# Non_Inverting_0603.net
KiCad netlist of a schematic drawn in EAGLE
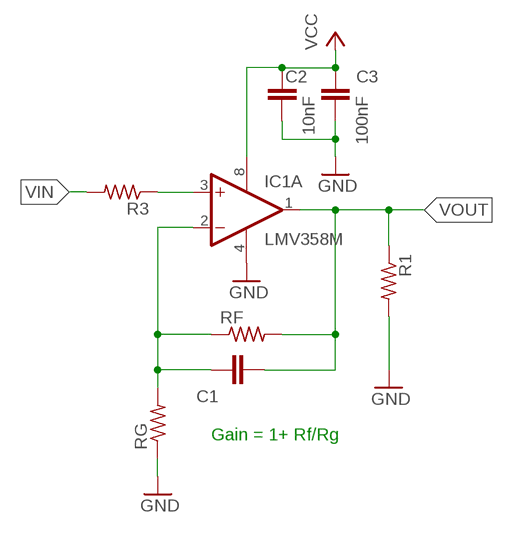
[diagram p0: schematic, sheet 1]

(export (version "E")
  (design (tool "Eeschema 10.0.6"))
  (components
    (comp (ref "C1")
      (value "C-EUC0603")
      (footprint "eagle-import:C0603")
      (libsource (lib "eagle-import") (part "C-EUC0603"))
    )
    (comp (ref "C2")
      (value "10nF")
      (footprint "eagle-import:C0603")
      (libsource (lib "eagle-import") (part "C-EUC0603"))
    )
    (comp (ref "C3")
      (value "100nF")
      (footprint "eagle-import:C0603")
      (libsource (lib "eagle-import") (part "C-EUC0603"))
    )
    (comp (ref "IC1")
      (value "LMV358M")
      (footprint "eagle-import:SO08")
      (libsource (lib "eagle-import") (part "LMV358?M"))
    )
    (comp (ref "R1")
      (value "R-US_R0603")
      (footprint "eagle-import:R0603")
      (libsource (lib "eagle-import") (part "R-US_R0603"))
    )
    (comp (ref "R3")
      (value "R-US_R0603")
      (footprint "eagle-import:R0603")
      (libsource (lib "eagle-import") (part "R-US_R0603"))
    )
    (comp (ref "RF")
      (value "R-US_R0603")
      (footprint "eagle-import:R0603")
      (libsource (lib "eagle-import") (part "R-US_R0603"))
    )
    (comp (ref "RG")
      (value "R-US_R0603")
      (footprint "eagle-import:R0603")
      (libsource (lib "eagle-import") (part "R-US_R0603"))
    )
  )
  (nets
    (net (code "1") (name "GND") (class "Default")
      (node (ref "C2") (pin "1") (pinfunction "1_1") (pintype "passive"))
      (node (ref "C3") (pin "1") (pinfunction "1_1") (pintype "passive"))
      (node (ref "IC1") (pin "4") (pinfunction "V-_4") (pintype "power_in"))
      (node (ref "R1") (pin "2") (pinfunction "2_2") (pintype "passive"))
      (node (ref "RG") (pin "1") (pinfunction "1_1") (pintype "passive"))
    )
    (net (code "2") (name "Net-(IC1A-+IN)") (class "Default")
      (node (ref "IC1") (pin "3") (pinfunction "+IN_3") (pintype "input"))
      (node (ref "R3") (pin "1") (pinfunction "1_1") (pintype "passive"))
    )
    (net (code "3") (name "Net-(IC1A--IN)") (class "Default")
      (node (ref "C1") (pin "1") (pinfunction "1_1") (pintype "passive"))
      (node (ref "IC1") (pin "2") (pinfunction "-IN_2") (pintype "input"))
      (node (ref "RF") (pin "1") (pinfunction "1_1") (pintype "passive"))
      (node (ref "RG") (pin "2") (pinfunction "2_2") (pintype "passive"))
    )
    (net (code "4") (name "VCC") (class "Default")
      (node (ref "C2") (pin "2") (pinfunction "2_2") (pintype "passive"))
      (node (ref "C3") (pin "2") (pinfunction "2_2") (pintype "passive"))
      (node (ref "IC1") (pin "8") (pinfunction "V+_8") (pintype "power_in"))
    )
    (net (code "5") (name "VIN") (class "Default")
      (node (ref "R3") (pin "2") (pinfunction "2_2") (pintype "passive"))
    )
    (net (code "6") (name "VOUT") (class "Default")
      (node (ref "C1") (pin "2") (pinfunction "2_2") (pintype "passive"))
      (node (ref "IC1") (pin "1") (pinfunction "OUT_1") (pintype "output"))
      (node (ref "R1") (pin "1") (pinfunction "1_1") (pintype "passive"))
      (node (ref "RF") (pin "2") (pinfunction "2_2") (pintype "passive"))
    )
  )
)
